# Mini_LED_Module.net
KiCad netlist of a schematic drawn in EAGLE
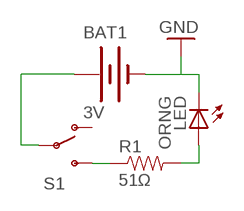
[diagram p0: schematic, sheet 1]

(export (version "E")
  (design (tool "Eeschema 10.0.6"))
  (components
    (comp (ref "BAT1")
      (value "3V")
      (footprint "eagle-import:BATTCON_20MM")
      (libsource (lib "eagle-import") (part "BATTERY20SMD"))
    )
    (comp (ref "LED")
      (value "ORNG")
      (footprint "eagle-import:LED5MM-KIT")
      (libsource (lib "eagle-import") (part "LED5MM-KIT"))
    )
    (comp (ref "R1")
      (value "51Ω")
      (footprint "eagle-import:0603-RES")
      (libsource (lib "eagle-import") (part "RESISTOR0603-RES"))
    )
    (comp (ref "S1")
      (value "SWITCH-SPDTKIT")
      (footprint "eagle-import:SWITCH-SPDT_KIT")
      (libsource (lib "eagle-import") (part "SWITCH-SPDTKIT"))
    )
  )
  (nets
    (net (code "1") (name "GND") (class "Default")
      (node (ref "BAT1") (pin "2") (pinfunction "-_2") (pintype "power_in"))
      (node (ref "LED") (pin "K") (pinfunction "C_K") (pintype "passive"))
    )
    (net (code "2") (name "Net-(BAT1-+)") (class "Default")
      (node (ref "BAT1") (pin "1") (pinfunction "+_1") (pintype "power_in"))
      (node (ref "S1") (pin "2") (pinfunction "P_2") (pintype "passive"))
    )
    (net (code "3") (name "Net-(LED-PadA)") (class "Default")
      (node (ref "LED") (pin "A") (pinfunction "A_A") (pintype "passive"))
      (node (ref "R1") (pin "2") (pinfunction "2_2") (pintype "passive"))
    )
    (net (code "4") (name "Net-(S1-S)") (class "Default")
      (node (ref "R1") (pin "1") (pinfunction "1_1") (pintype "passive"))
      (node (ref "S1") (pin "3") (pinfunction "S_3") (pintype "passive"))
    )
    (net (code "5") (name "unconnected-(S1-O-Pad1)") (class "Default")
      (node (ref "S1") (pin "1") (pinfunction "O_1") (pintype "passive"))
    )
  )
)
